# DIDV_-_Expansao_10.net
KiCad netlist of a schematic drawn in EAGLE
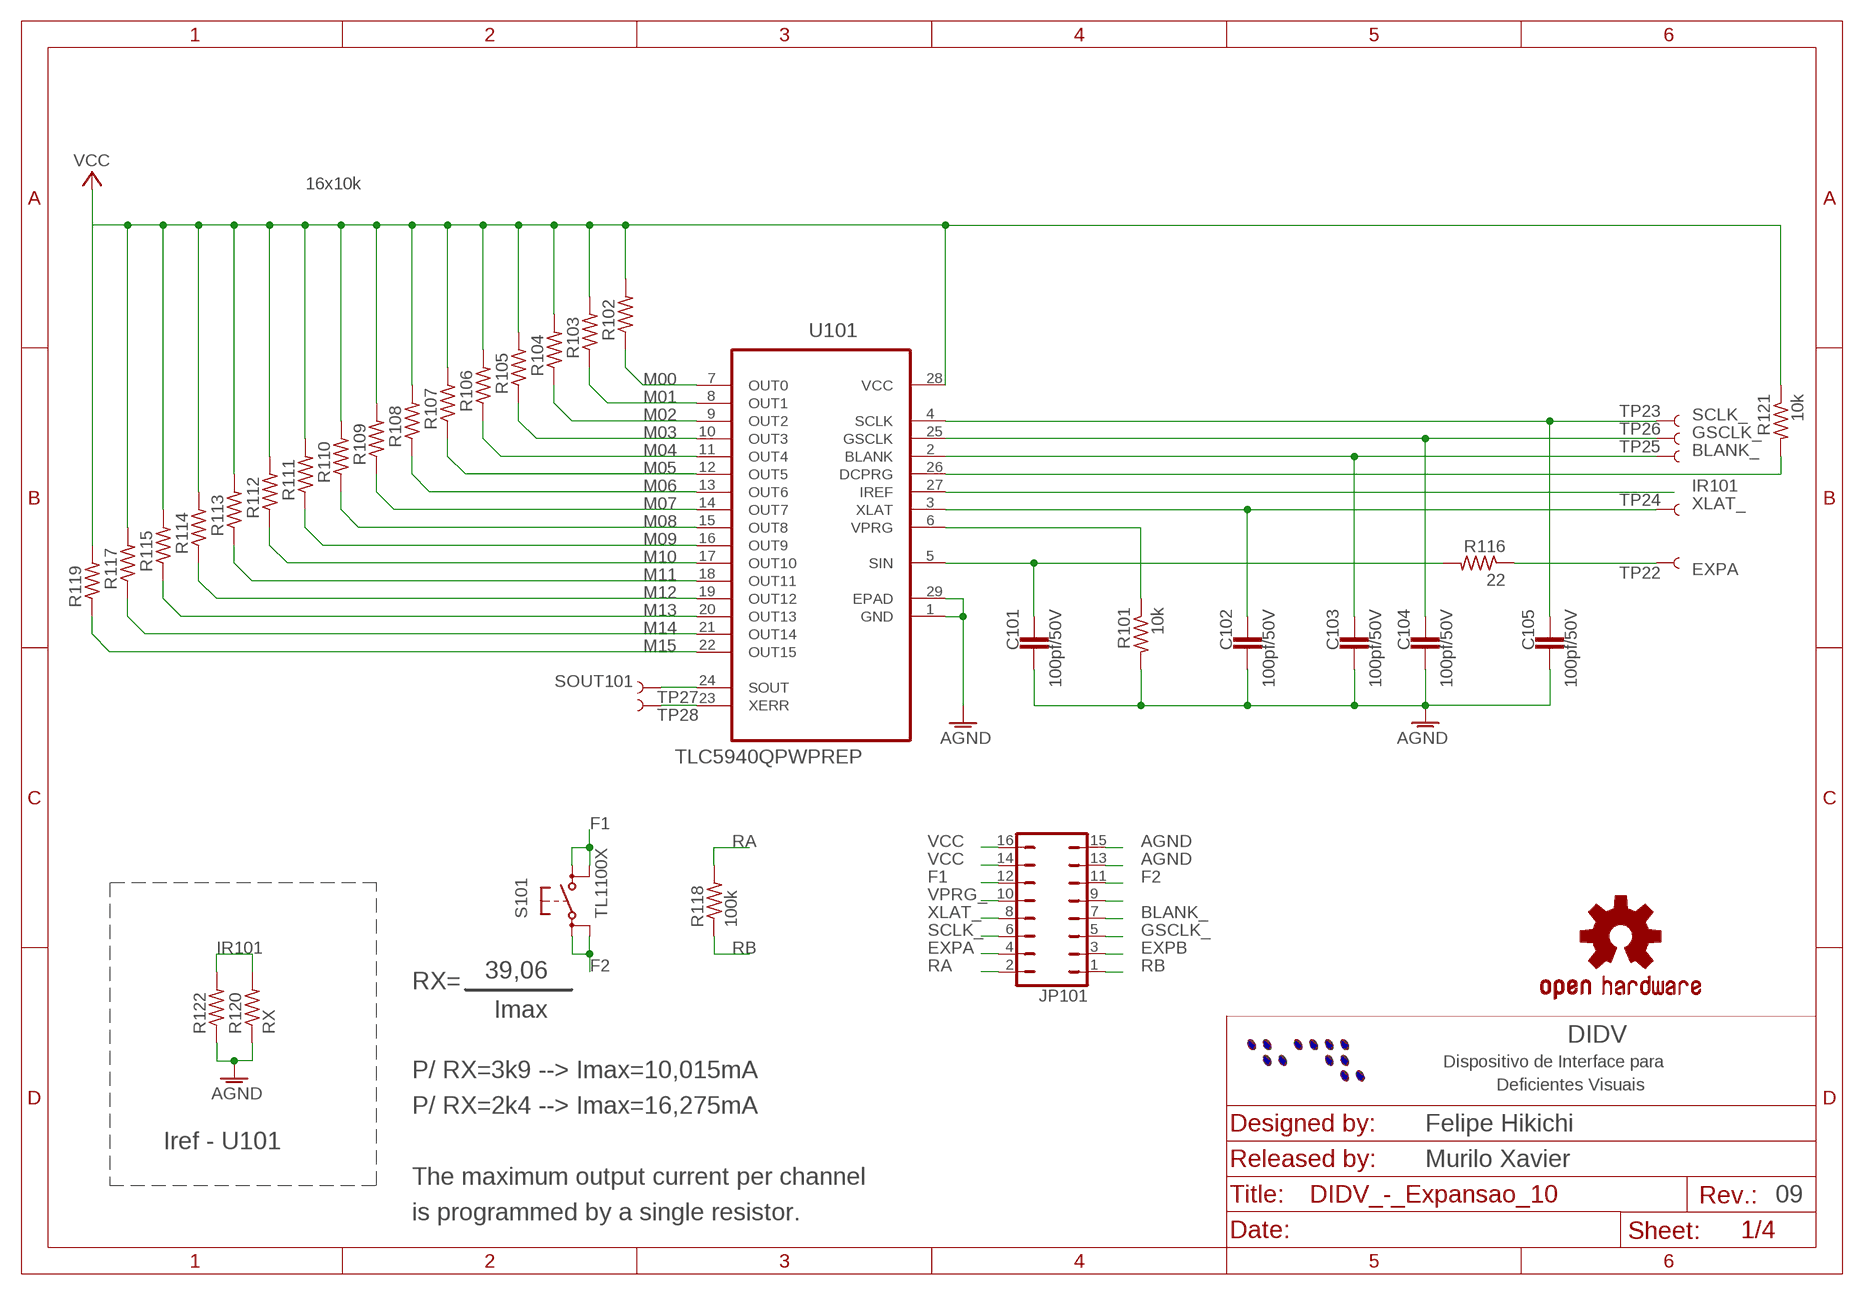
[diagram p0: schematic, sheet 1]
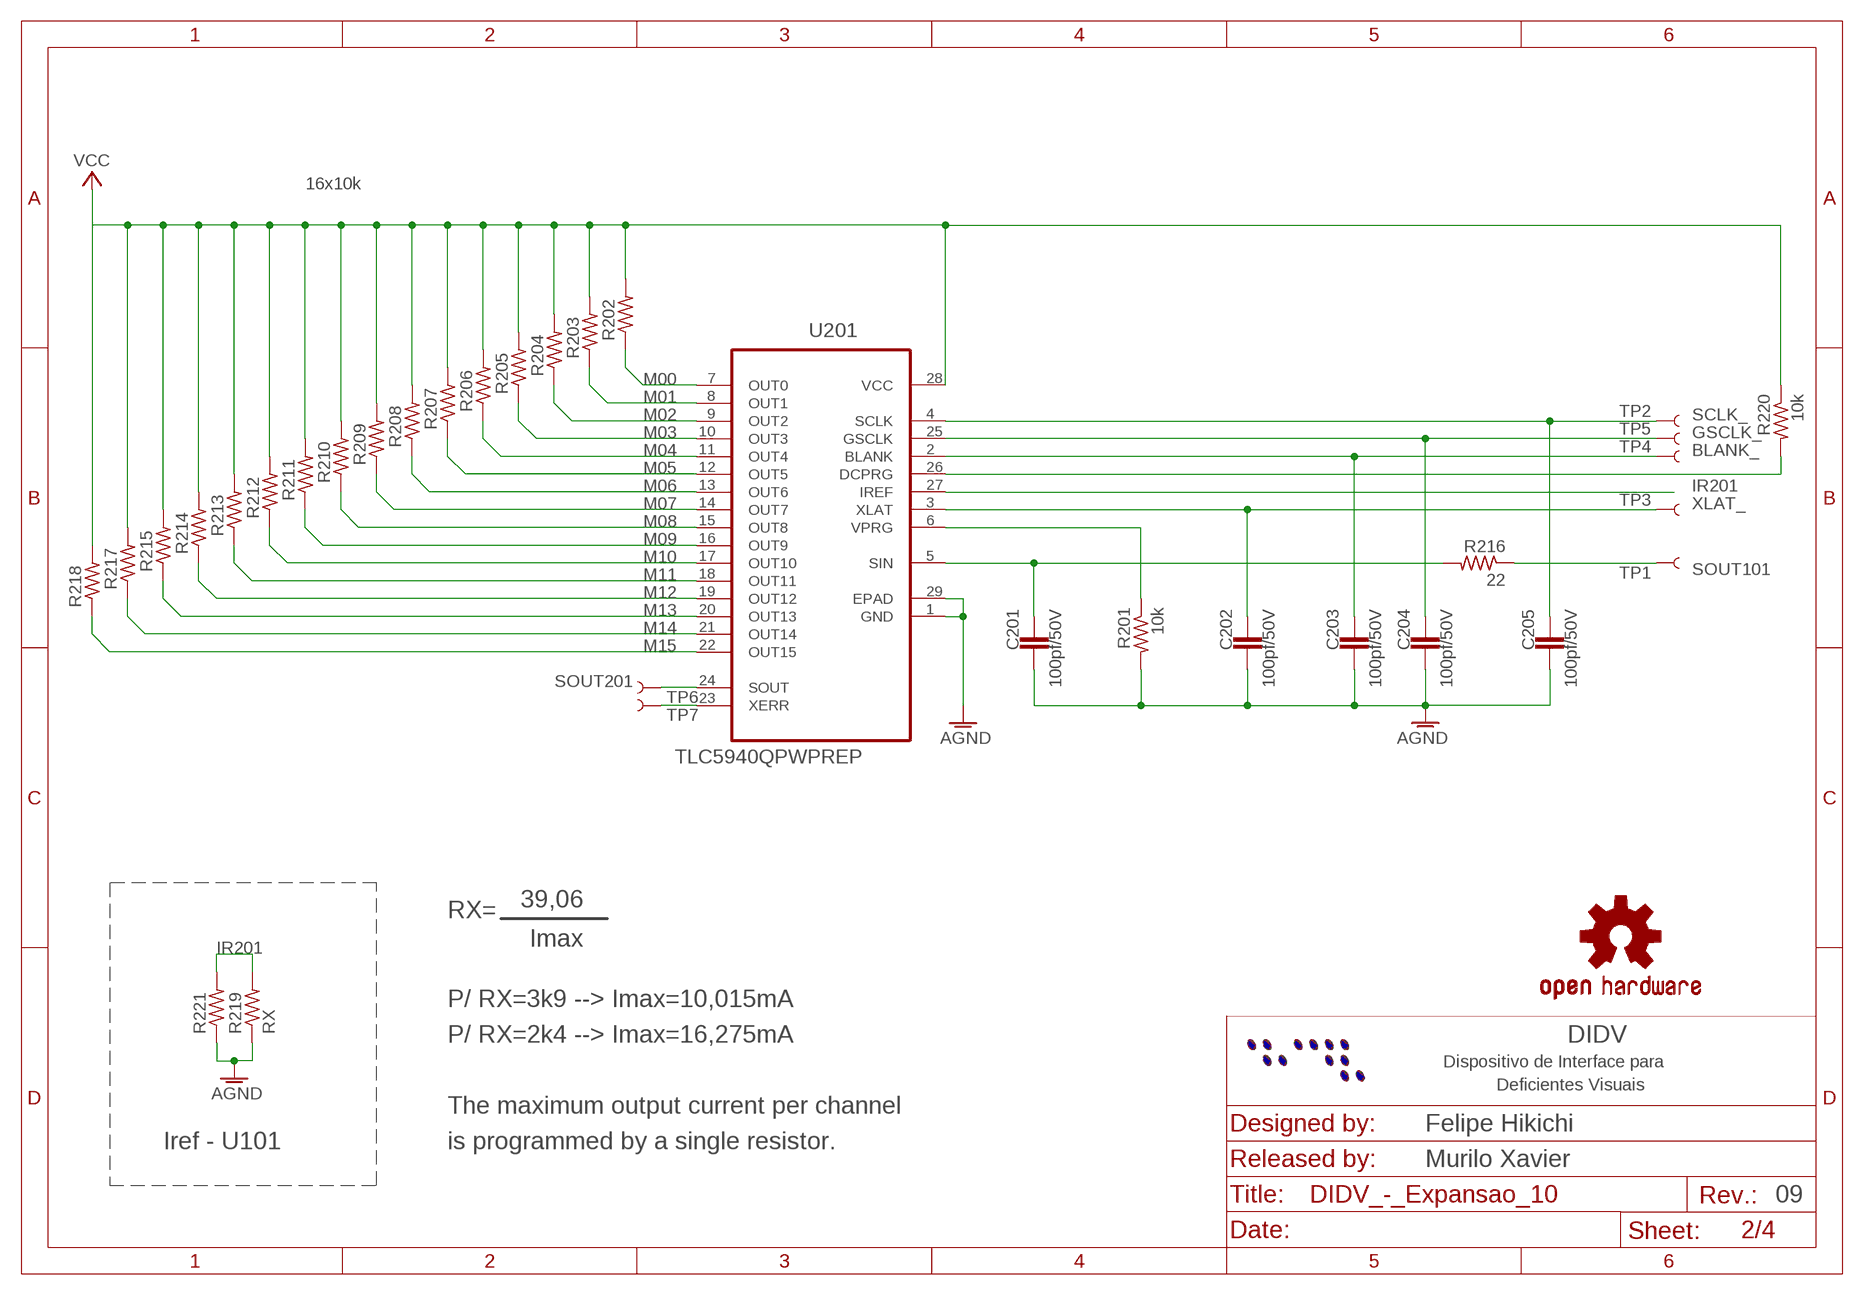
[diagram p1: schematic, sheet 2]
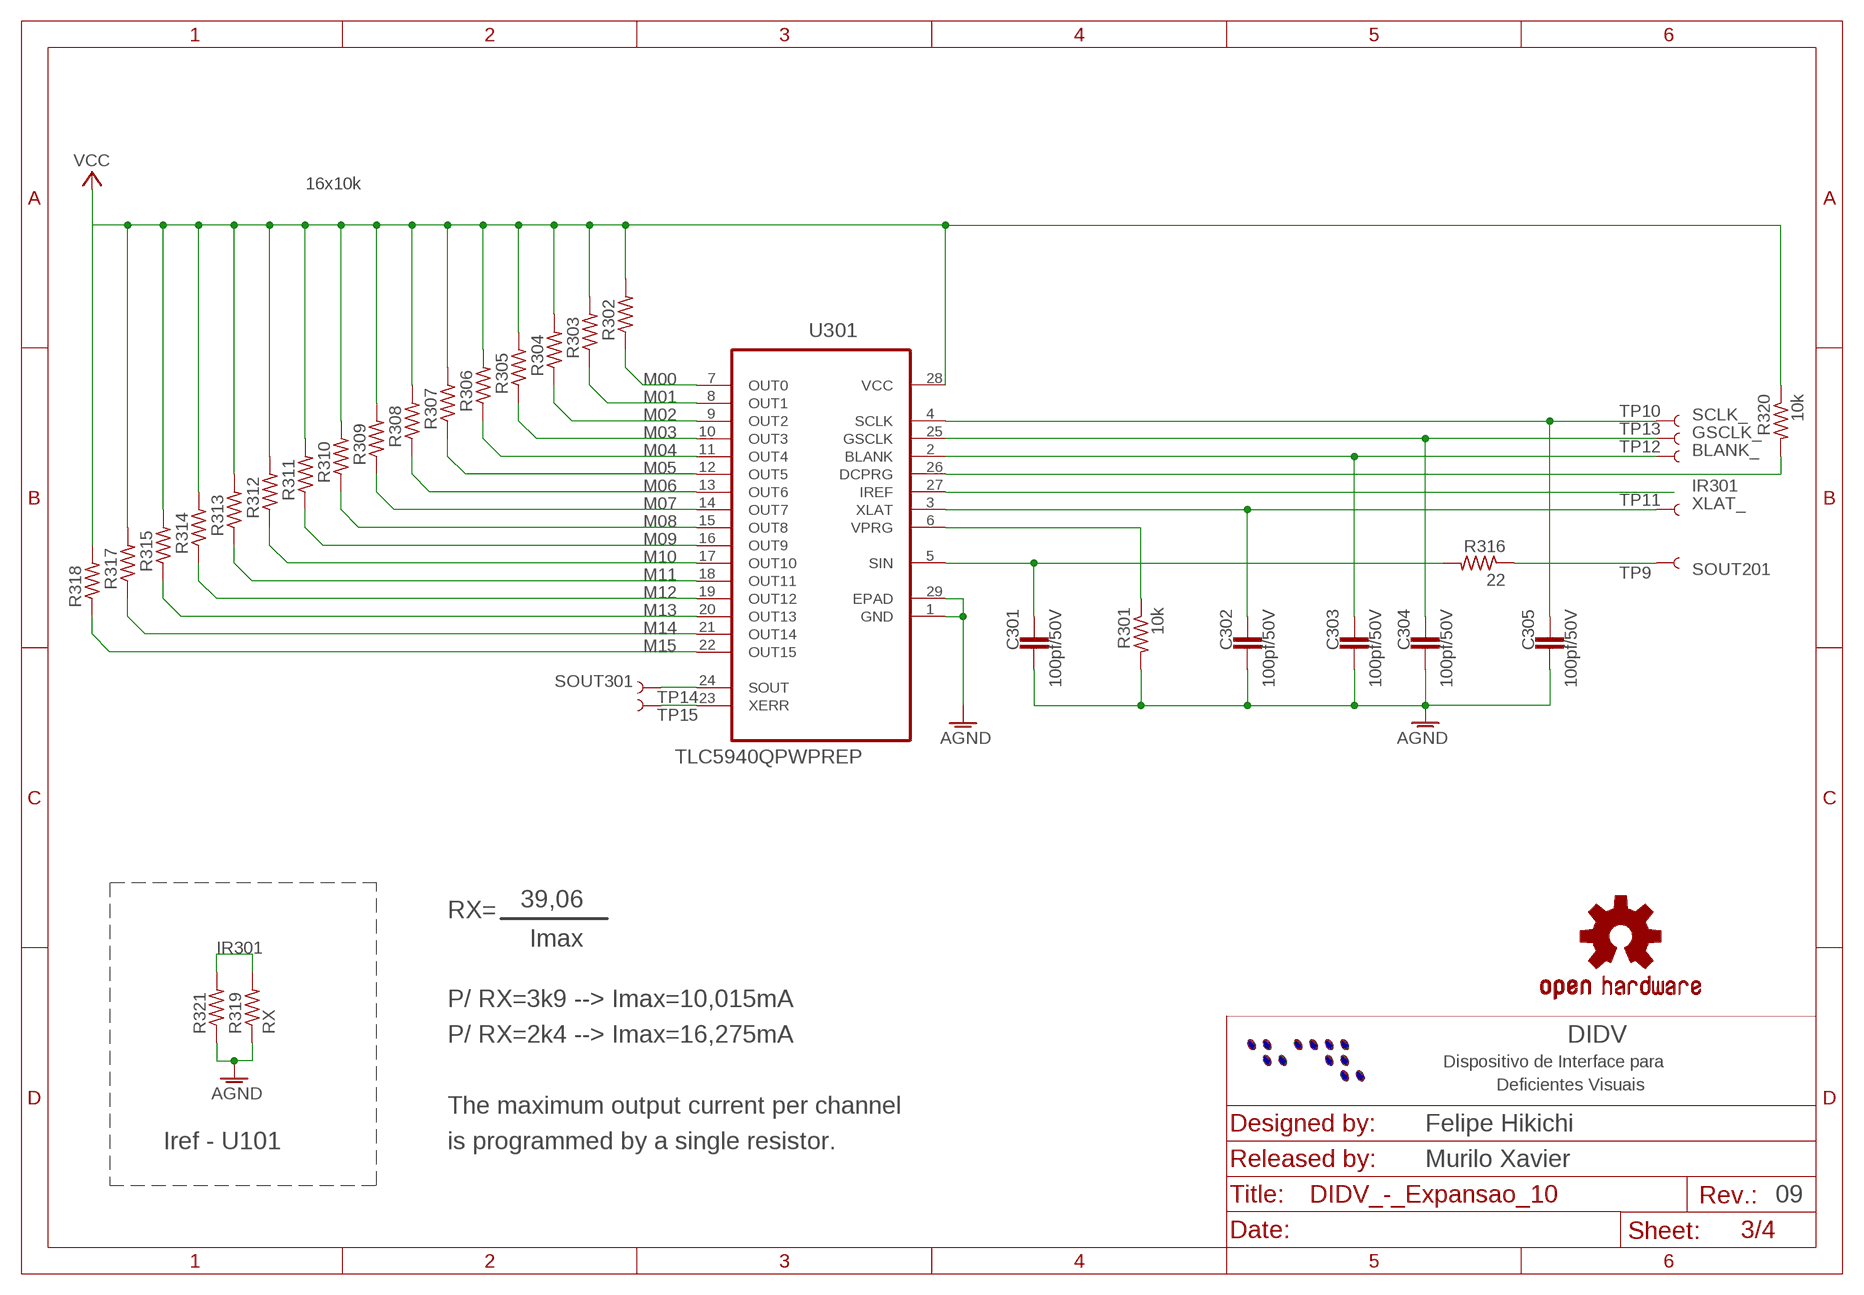
[diagram p2: schematic, sheet 3]
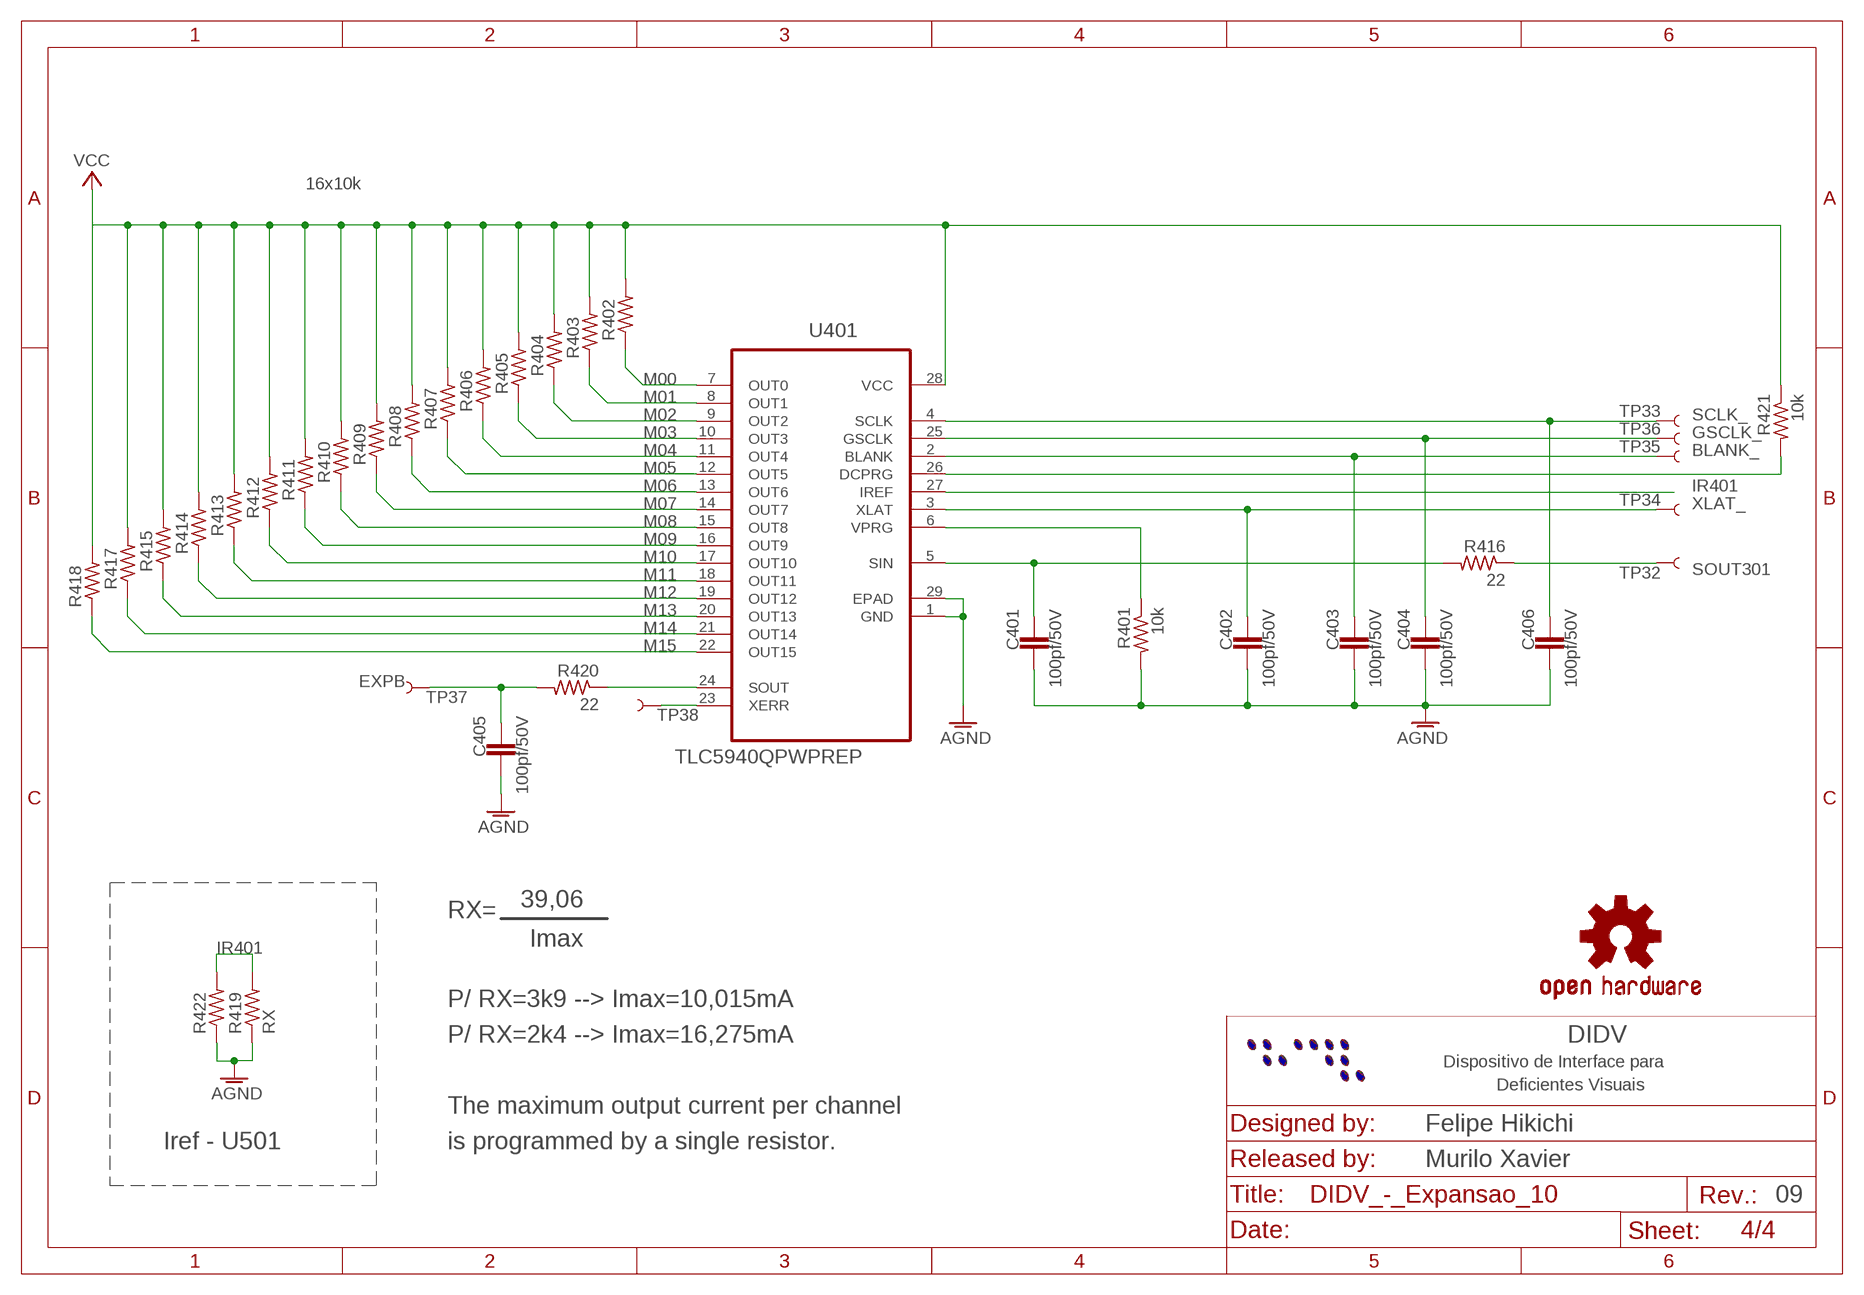
[diagram p3: schematic, sheet 4]

(export (version "E")
  (design (tool "Eeschema 10.0.6"))
  (components
    (comp (ref "C201")
      (value "100pf/50V")
      (footprint "eagle-import:C0603K")
      (libsource (lib "eagle-import") (part "C-EUC0603K"))
    )
    (comp (ref "C202")
      (value "100pf/50V")
      (footprint "eagle-import:C0603K")
      (libsource (lib "eagle-import") (part "C-EUC0603K"))
    )
    (comp (ref "C203")
      (value "100pf/50V")
      (footprint "eagle-import:C0603K")
      (libsource (lib "eagle-import") (part "C-EUC0603K"))
    )
    (comp (ref "C204")
      (value "100pf/50V")
      (footprint "eagle-import:C0603K")
      (libsource (lib "eagle-import") (part "C-EUC0603K"))
    )
    (comp (ref "C205")
      (value "100pf/50V")
      (footprint "eagle-import:C0603K")
      (libsource (lib "eagle-import") (part "C-EUC0603K"))
    )
    (comp (ref "LOGO201")
      (value "OSHW-LOGOM")
      (footprint "eagle-import:OSHW-LOGO-M")
      (libsource (lib "eagle-import") (part "OSHW-LOGOM"))
    )
    (comp (ref "R201")
      (value "10k")
      (footprint "eagle-import:R0603")
      (libsource (lib "eagle-import") (part "R-US_R0603"))
    )
    (comp (ref "R202")
      (value "R-US_R0805")
      (footprint "eagle-import:R0805")
      (libsource (lib "eagle-import") (part "R-US_R0805"))
    )
    (comp (ref "R203")
      (value "R-US_R0805")
      (footprint "eagle-import:R0805")
      (libsource (lib "eagle-import") (part "R-US_R0805"))
    )
    (comp (ref "R204")
      (value "R-US_R0805")
      (footprint "eagle-import:R0805")
      (libsource (lib "eagle-import") (part "R-US_R0805"))
    )
    (comp (ref "R205")
      (value "R-US_R0805")
      (footprint "eagle-import:R0805")
      (libsource (lib "eagle-import") (part "R-US_R0805"))
    )
    (comp (ref "R206")
      (value "R-US_R0805")
      (footprint "eagle-import:R0805")
      (libsource (lib "eagle-import") (part "R-US_R0805"))
    )
    (comp (ref "R207")
      (value "R-US_R0805")
      (footprint "eagle-import:R0805")
      (libsource (lib "eagle-import") (part "R-US_R0805"))
    )
    (comp (ref "R208")
      (value "R-US_R0805")
      (footprint "eagle-import:R0805")
      (libsource (lib "eagle-import") (part "R-US_R0805"))
    )
    (comp (ref "R209")
      (value "R-US_R0805")
      (footprint "eagle-import:R0805")
      (libsource (lib "eagle-import") (part "R-US_R0805"))
    )
    (comp (ref "R210")
      (value "R-US_R0805")
      (footprint "eagle-import:R0805")
      (libsource (lib "eagle-import") (part "R-US_R0805"))
    )
    (comp (ref "R211")
      (value "R-US_R0805")
      (footprint "eagle-import:R0805")
      (libsource (lib "eagle-import") (part "R-US_R0805"))
    )
    (comp (ref "R212")
      (value "R-US_R0805")
      (footprint "eagle-import:R0805")
      (libsource (lib "eagle-import") (part "R-US_R0805"))
    )
    (comp (ref "R213")
      (value "R-US_R0805")
      (footprint "eagle-import:R0805")
      (libsource (lib "eagle-import") (part "R-US_R0805"))
    )
    (comp (ref "R214")
      (value "R-US_R0805")
      (footprint "eagle-import:R0805")
      (libsource (lib "eagle-import") (part "R-US_R0805"))
    )
    (comp (ref "R215")
      (value "R-US_R0805")
      (footprint "eagle-import:R0805")
      (libsource (lib "eagle-import") (part "R-US_R0805"))
    )
    (comp (ref "R216")
      (value "22")
      (footprint "eagle-import:R0603")
      (libsource (lib "eagle-import") (part "R-US_R0603"))
    )
    (comp (ref "R217")
      (value "R-US_R0805")
      (footprint "eagle-import:R0805")
      (libsource (lib "eagle-import") (part "R-US_R0805"))
    )
    (comp (ref "R218")
      (value "R-US_R0805")
      (footprint "eagle-import:R0805")
      (libsource (lib "eagle-import") (part "R-US_R0805"))
    )
    (comp (ref "R219")
      (value "RX")
      (footprint "eagle-import:R0805")
      (libsource (lib "eagle-import") (part "R-US_R0805"))
    )
    (comp (ref "R220")
      (value "10k")
      (footprint "eagle-import:R0603")
      (libsource (lib "eagle-import") (part "R-US_R0603"))
    )
    (comp (ref "R221")
      (value "R-US_R0805")
      (footprint "eagle-import:R0805")
      (libsource (lib "eagle-import") (part "R-US_R0805"))
    )
    (comp (ref "TP1")
      (value "TEST-POINT3X4")
      (footprint "eagle-import:PAD.03X.04")
      (libsource (lib "eagle-import") (part "TEST-POINT3X4"))
    )
    (comp (ref "TP2")
      (value "TEST-POINT3X4")
      (footprint "eagle-import:PAD.03X.04")
      (libsource (lib "eagle-import") (part "TEST-POINT3X4"))
    )
    (comp (ref "TP3")
      (value "TEST-POINT3X4")
      (footprint "eagle-import:PAD.03X.04")
      (libsource (lib "eagle-import") (part "TEST-POINT3X4"))
    )
    (comp (ref "TP4")
      (value "TEST-POINT3X4")
      (footprint "eagle-import:PAD.03X.04")
      (libsource (lib "eagle-import") (part "TEST-POINT3X4"))
    )
    (comp (ref "TP5")
      (value "TEST-POINT3X4")
      (footprint "eagle-import:PAD.03X.04")
      (libsource (lib "eagle-import") (part "TEST-POINT3X4"))
    )
    (comp (ref "TP6")
      (value "TEST-POINT3X4")
      (footprint "eagle-import:PAD.03X.04")
      (libsource (lib "eagle-import") (part "TEST-POINT3X4"))
    )
    (comp (ref "TP7")
      (value "TEST-POINT3X4")
      (footprint "eagle-import:PAD.03X.04")
      (libsource (lib "eagle-import") (part "TEST-POINT3X4"))
    )
    (comp (ref "U201")
      (value "TLC5940QPWPREP")
      (footprint "eagle-import:SOP65P640X120-29N")
      (libsource (lib "eagle-import") (part "TLC5940QPWPREP"))
    )
    (comp (ref "C301")
      (value "100pf/50V")
      (footprint "eagle-import:C0603K")
      (libsource (lib "eagle-import") (part "C-EUC0603K"))
    )
    (comp (ref "C302")
      (value "100pf/50V")
      (footprint "eagle-import:C0603K")
      (libsource (lib "eagle-import") (part "C-EUC0603K"))
    )
    (comp (ref "C303")
      (value "100pf/50V")
      (footprint "eagle-import:C0603K")
      (libsource (lib "eagle-import") (part "C-EUC0603K"))
    )
    (comp (ref "C304")
      (value "100pf/50V")
      (footprint "eagle-import:C0603K")
      (libsource (lib "eagle-import") (part "C-EUC0603K"))
    )
    (comp (ref "C305")
      (value "100pf/50V")
      (footprint "eagle-import:C0603K")
      (libsource (lib "eagle-import") (part "C-EUC0603K"))
    )
    (comp (ref "LOGO301")
      (value "OSHW-LOGOM")
      (footprint "eagle-import:OSHW-LOGO-M")
      (libsource (lib "eagle-import") (part "OSHW-LOGOM"))
    )
    (comp (ref "R301")
      (value "10k")
      (footprint "eagle-import:R0603")
      (libsource (lib "eagle-import") (part "R-US_R0603"))
    )
    (comp (ref "R302")
      (value "R-US_R0805")
      (footprint "eagle-import:R0805")
      (libsource (lib "eagle-import") (part "R-US_R0805"))
    )
    (comp (ref "R303")
      (value "R-US_R0805")
      (footprint "eagle-import:R0805")
      (libsource (lib "eagle-import") (part "R-US_R0805"))
    )
    (comp (ref "R304")
      (value "R-US_R0805")
      (footprint "eagle-import:R0805")
      (libsource (lib "eagle-import") (part "R-US_R0805"))
    )
    (comp (ref "R305")
      (value "R-US_R0805")
      (footprint "eagle-import:R0805")
      (libsource (lib "eagle-import") (part "R-US_R0805"))
    )
    (comp (ref "R306")
      (value "R-US_R0805")
      (footprint "eagle-import:R0805")
      (libsource (lib "eagle-import") (part "R-US_R0805"))
    )
    (comp (ref "R307")
      (value "R-US_R0805")
      (footprint "eagle-import:R0805")
      (libsource (lib "eagle-import") (part "R-US_R0805"))
    )
    (comp (ref "R308")
      (value "R-US_R0805")
      (footprint "eagle-import:R0805")
      (libsource (lib "eagle-import") (part "R-US_R0805"))
    )
    (comp (ref "R309")
      (value "R-US_R0805")
      (footprint "eagle-import:R0805")
      (libsource (lib "eagle-import") (part "R-US_R0805"))
    )
    (comp (ref "R310")
      (value "R-US_R0805")
      (footprint "eagle-import:R0805")
      (libsource (lib "eagle-import") (part "R-US_R0805"))
    )
    (comp (ref "R311")
      (value "R-US_R0805")
      (footprint "eagle-import:R0805")
      (libsource (lib "eagle-import") (part "R-US_R0805"))
    )
    (comp (ref "R312")
      (value "R-US_R0805")
      (footprint "eagle-import:R0805")
      (libsource (lib "eagle-import") (part "R-US_R0805"))
    )
    (comp (ref "R313")
      (value "R-US_R0805")
      (footprint "eagle-import:R0805")
      (libsource (lib "eagle-import") (part "R-US_R0805"))
    )
    (comp (ref "R314")
      (value "R-US_R0805")
      (footprint "eagle-import:R0805")
      (libsource (lib "eagle-import") (part "R-US_R0805"))
    )
    (comp (ref "R315")
      (value "R-US_R0805")
      (footprint "eagle-import:R0805")
      (libsource (lib "eagle-import") (part "R-US_R0805"))
    )
    (comp (ref "R316")
      (value "22")
      (footprint "eagle-import:R0603")
      (libsource (lib "eagle-import") (part "R-US_R0603"))
    )
    (comp (ref "R317")
      (value "R-US_R0805")
      (footprint "eagle-import:R0805")
      (libsource (lib "eagle-import") (part "R-US_R0805"))
    )
    (comp (ref "R318")
      (value "R-US_R0805")
      (footprint "eagle-import:R0805")
      (libsource (lib "eagle-import") (part "R-US_R0805"))
    )
    (comp (ref "R319")
      (value "RX")
      (footprint "eagle-import:R0805")
      (libsource (lib "eagle-import") (part "R-US_R0805"))
    )
    (comp (ref "R320")
      (value "10k")
      (footprint "eagle-import:R0603")
      (libsource (lib "eagle-import") (part "R-US_R0603"))
    )
    (comp (ref "R321")
      (value "R-US_R0805")
      (footprint "eagle-import:R0805")
      (libsource (lib "eagle-import") (part "R-US_R0805"))
    )
    (comp (ref "TP9")
      (value "TEST-POINT3X4")
      (footprint "eagle-import:PAD.03X.04")
      (libsource (lib "eagle-import") (part "TEST-POINT3X4"))
    )
    (comp (ref "TP10")
      (value "TEST-POINT3X4")
      (footprint "eagle-import:PAD.03X.04")
      (libsource (lib "eagle-import") (part "TEST-POINT3X4"))
    )
    (comp (ref "TP11")
      (value "TEST-POINT3X4")
      (footprint "eagle-import:PAD.03X.04")
      (libsource (lib "eagle-import") (part "TEST-POINT3X4"))
    )
    (comp (ref "TP12")
      (value "TEST-POINT3X4")
      (footprint "eagle-import:PAD.03X.04")
      (libsource (lib "eagle-import") (part "TEST-POINT3X4"))
    )
    (comp (ref "TP13")
      (value "TEST-POINT3X4")
      (footprint "eagle-import:PAD.03X.04")
      (libsource (lib "eagle-import") (part "TEST-POINT3X4"))
    )
    (comp (ref "TP14")
      (value "TEST-POINT3X4")
      (footprint "eagle-import:PAD.03X.04")
      (libsource (lib "eagle-import") (part "TEST-POINT3X4"))
    )
    (comp (ref "TP15")
      (value "TEST-POINT3X4")
      (footprint "eagle-import:PAD.03X.04")
      (libsource (lib "eagle-import") (part "TEST-POINT3X4"))
    )
    (comp (ref "U301")
      (value "TLC5940QPWPREP")
      (footprint "eagle-import:SOP65P640X120-29N")
      (libsource (lib "eagle-import") (part "TLC5940QPWPREP"))
    )
    (comp (ref "C101")
      (value "100pf/50V")
      (footprint "eagle-import:C0603K")
      (libsource (lib "eagle-import") (part "C-EUC0603K"))
    )
    (comp (ref "C102")
      (value "100pf/50V")
      (footprint "eagle-import:C0603K")
      (libsource (lib "eagle-import") (part "C-EUC0603K"))
    )
    (comp (ref "C103")
      (value "100pf/50V")
      (footprint "eagle-import:C0603K")
      (libsource (lib "eagle-import") (part "C-EUC0603K"))
    )
    (comp (ref "C104")
      (value "100pf/50V")
      (footprint "eagle-import:C0603K")
      (libsource (lib "eagle-import") (part "C-EUC0603K"))
    )
    (comp (ref "C105")
      (value "100pf/50V")
      (footprint "eagle-import:C0603K")
      (libsource (lib "eagle-import") (part "C-EUC0603K"))
    )
    (comp (ref "JP101")
      (value "JP8Q")
      (footprint "eagle-import:JP8Q")
      (libsource (lib "eagle-import") (part "JP8Q"))
    )
    (comp (ref "LOGO101")
      (value "OSHW-LOGOM")
      (footprint "eagle-import:OSHW-LOGO-M")
      (libsource (lib "eagle-import") (part "OSHW-LOGOM"))
    )
    (comp (ref "R101")
      (value "10k")
      (footprint "eagle-import:R0603")
      (libsource (lib "eagle-import") (part "R-US_R0603"))
    )
    (comp (ref "R102")
      (value "R-US_R0805")
      (footprint "eagle-import:R0805")
      (libsource (lib "eagle-import") (part "R-US_R0805"))
    )
    (comp (ref "R103")
      (value "R-US_R0805")
      (footprint "eagle-import:R0805")
      (libsource (lib "eagle-import") (part "R-US_R0805"))
    )
    (comp (ref "R104")
      (value "R-US_R0805")
      (footprint "eagle-import:R0805")
      (libsource (lib "eagle-import") (part "R-US_R0805"))
    )
    (comp (ref "R105")
      (value "R-US_R0805")
      (footprint "eagle-import:R0805")
      (libsource (lib "eagle-import") (part "R-US_R0805"))
    )
    (comp (ref "R106")
      (value "R-US_R0805")
      (footprint "eagle-import:R0805")
      (libsource (lib "eagle-import") (part "R-US_R0805"))
    )
    (comp (ref "R107")
      (value "R-US_R0805")
      (footprint "eagle-import:R0805")
      (libsource (lib "eagle-import") (part "R-US_R0805"))
    )
    (comp (ref "R108")
      (value "R-US_R0805")
      (footprint "eagle-import:R0805")
      (libsource (lib "eagle-import") (part "R-US_R0805"))
    )
    (comp (ref "R109")
      (value "R-US_R0805")
      (footprint "eagle-import:R0805")
      (libsource (lib "eagle-import") (part "R-US_R0805"))
    )
    (comp (ref "R110")
      (value "R-US_R0805")
      (footprint "eagle-import:R0805")
      (libsource (lib "eagle-import") (part "R-US_R0805"))
    )
    (comp (ref "R111")
      (value "R-US_R0805")
      (footprint "eagle-import:R0805")
      (libsource (lib "eagle-import") (part "R-US_R0805"))
    )
    (comp (ref "R112")
      (value "R-US_R0805")
      (footprint "eagle-import:R0805")
      (libsource (lib "eagle-import") (part "R-US_R0805"))
    )
    (comp (ref "R113")
      (value "R-US_R0805")
      (footprint "eagle-import:R0805")
      (libsource (lib "eagle-import") (part "R-US_R0805"))
    )
    (comp (ref "R114")
      (value "R-US_R0805")
      (footprint "eagle-import:R0805")
      (libsource (lib "eagle-import") (part "R-US_R0805"))
    )
    (comp (ref "R115")
      (value "R-US_R0805")
      (footprint "eagle-import:R0805")
      (libsource (lib "eagle-import") (part "R-US_R0805"))
    )
    (comp (ref "R116")
      (value "22")
      (footprint "eagle-import:R0603")
      (libsource (lib "eagle-import") (part "R-US_R0603"))
    )
    (comp (ref "R117")
      (value "R-US_R0805")
      (footprint "eagle-import:R0805")
      (libsource (lib "eagle-import") (part "R-US_R0805"))
    )
    (comp (ref "R118")
      (value "100k")
      (footprint "eagle-import:R0805")
      (libsource (lib "eagle-import") (part "R-US_R0805"))
    )
    (comp (ref "R119")
      (value "R-US_R0805")
      (footprint "eagle-import:R0805")
      (libsource (lib "eagle-import") (part "R-US_R0805"))
    )
    (comp (ref "R120")
      (value "RX")
      (footprint "eagle-import:R0805")
      (libsource (lib "eagle-import") (part "R-US_R0805"))
    )
    (comp (ref "R121")
      (value "10k")
      (footprint "eagle-import:R0603")
      (libsource (lib "eagle-import") (part "R-US_R0603"))
    )
    (comp (ref "R122")
      (value "R-US_R0805")
      (footprint "eagle-import:R0805")
      (libsource (lib "eagle-import") (part "R-US_R0805"))
    )
    (comp (ref "S101")
      (value "TL1100X")
      (footprint "eagle-import:TL1100X")
      (libsource (lib "eagle-import") (part "TL1100X"))
    )
    (comp (ref "TP22")
      (value "TEST-POINT3X4")
      (footprint "eagle-import:PAD.03X.04")
      (libsource (lib "eagle-import") (part "TEST-POINT3X4"))
    )
    (comp (ref "TP23")
      (value "TEST-POINT3X4")
      (footprint "eagle-import:PAD.03X.04")
      (libsource (lib "eagle-import") (part "TEST-POINT3X4"))
    )
    (comp (ref "TP24")
      (value "TEST-POINT3X4")
      (footprint "eagle-import:PAD.03X.04")
      (libsource (lib "eagle-import") (part "TEST-POINT3X4"))
    )
    (comp (ref "TP25")
      (value "TEST-POINT3X4")
      (footprint "eagle-import:PAD.03X.04")
      (libsource (lib "eagle-import") (part "TEST-POINT3X4"))
    )
    (comp (ref "TP26")
      (value "TEST-POINT3X4")
      (footprint "eagle-import:PAD.03X.04")
      (libsource (lib "eagle-import") (part "TEST-POINT3X4"))
    )
    (comp (ref "TP27")
      (value "TEST-POINT3X4")
      (footprint "eagle-import:PAD.03X.04")
      (libsource (lib "eagle-import") (part "TEST-POINT3X4"))
    )
    (comp (ref "TP28")
      (value "TEST-POINT3X4")
      (footprint "eagle-import:PAD.03X.04")
      (libsource (lib "eagle-import") (part "TEST-POINT3X4"))
    )
    (comp (ref "U101")
      (value "TLC5940QPWPREP")
      (footprint "eagle-import:SOP65P640X120-29N")
      (libsource (lib "eagle-import") (part "TLC5940QPWPREP"))
    )
    (comp (ref "C401")
      (value "100pf/50V")
      (footprint "eagle-import:C0603K")
      (libsource (lib "eagle-import") (part "C-EUC0603K"))
    )
    (comp (ref "C402")
      (value "100pf/50V")
      (footprint "eagle-import:C0603K")
      (libsource (lib "eagle-import") (part "C-EUC0603K"))
    )
    (comp (ref "C403")
      (value "100pf/50V")
      (footprint "eagle-import:C0603K")
      (libsource (lib "eagle-import") (part "C-EUC0603K"))
    )
    (comp (ref "C404")
      (value "100pf/50V")
      (footprint "eagle-import:C0603K")
      (libsource (lib "eagle-import") (part "C-EUC0603K"))
    )
    (comp (ref "C405")
      (value "100pf/50V")
      (footprint "eagle-import:C0603K")
      (libsource (lib "eagle-import") (part "C-EUC0603K"))
    )
    (comp (ref "C406")
      (value "100pf/50V")
      (footprint "eagle-import:C0603K")
      (libsource (lib "eagle-import") (part "C-EUC0603K"))
    )
    (comp (ref "LOGO401")
      (value "OSHW-LOGOM")
      (footprint "eagle-import:OSHW-LOGO-M")
      (libsource (lib "eagle-import") (part "OSHW-LOGOM"))
    )
    (comp (ref "R401")
      (value "10k")
      (footprint "eagle-import:R0603")
      (libsource (lib "eagle-import") (part "R-US_R0603"))
    )
    (comp (ref "R402")
      (value "R-US_R0805")
      (footprint "eagle-import:R0805")
      (libsource (lib "eagle-import") (part "R-US_R0805"))
    )
    (comp (ref "R403")
      (value "R-US_R0805")
      (footprint "eagle-import:R0805")
      (libsource (lib "eagle-import") (part "R-US_R0805"))
    )
    (comp (ref "R404")
      (value "R-US_R0805")
      (footprint "eagle-import:R0805")
      (libsource (lib "eagle-import") (part "R-US_R0805"))
    )
    (comp (ref "R405")
      (value "R-US_R0805")
      (footprint "eagle-import:R0805")
      (libsource (lib "eagle-import") (part "R-US_R0805"))
    )
    (comp (ref "R406")
      (value "R-US_R0805")
      (footprint "eagle-import:R0805")
      (libsource (lib "eagle-import") (part "R-US_R0805"))
    )
    (comp (ref "R407")
      (value "R-US_R0805")
      (footprint "eagle-import:R0805")
      (libsource (lib "eagle-import") (part "R-US_R0805"))
    )
    (comp (ref "R408")
      (value "R-US_R0805")
      (footprint "eagle-import:R0805")
      (libsource (lib "eagle-import") (part "R-US_R0805"))
    )
    (comp (ref "R409")
      (value "R-US_R0805")
      (footprint "eagle-import:R0805")
      (libsource (lib "eagle-import") (part "R-US_R0805"))
    )
    (comp (ref "R410")
      (value "R-US_R0805")
      (footprint "eagle-import:R0805")
      (libsource (lib "eagle-import") (part "R-US_R0805"))
    )
    (comp (ref "R411")
      (value "R-US_R0805")
      (footprint "eagle-import:R0805")
      (libsource (lib "eagle-import") (part "R-US_R0805"))
    )
    (comp (ref "R412")
      (value "R-US_R0805")
      (footprint "eagle-import:R0805")
      (libsource (lib "eagle-import") (part "R-US_R0805"))
    )
    (comp (ref "R413")
      (value "R-US_R0805")
      (footprint "eagle-import:R0805")
      (libsource (lib "eagle-import") (part "R-US_R0805"))
    )
    (comp (ref "R414")
      (value "R-US_R0805")
      (footprint "eagle-import:R0805")
      (libsource (lib "eagle-import") (part "R-US_R0805"))
    )
    (comp (ref "R415")
      (value "R-US_R0805")
      (footprint "eagle-import:R0805")
      (libsource (lib "eagle-import") (part "R-US_R0805"))
    )
    (comp (ref "R416")
      (value "22")
      (footprint "eagle-import:R0603")
      (libsource (lib "eagle-import") (part "R-US_R0603"))
    )
    (comp (ref "R417")
      (value "R-US_R0805")
      (footprint "eagle-import:R0805")
      (libsource (lib "eagle-import") (part "R-US_R0805"))
    )
    (comp (ref "R418")
      (value "R-US_R0805")
      (footprint "eagle-import:R0805")
      (libsource (lib "eagle-import") (part "R-US_R0805"))
    )
    (comp (ref "R419")
      (value "RX")
      (footprint "eagle-import:R0805")
      (libsource (lib "eagle-import") (part "R-US_R0805"))
    )
    (comp (ref "R420")
      (value "22")
      (footprint "eagle-import:R0603")
      (libsource (lib "eagle-import") (part "R-US_R0603"))
    )
    (comp (ref "R421")
      (value "10k")
      (footprint "eagle-import:R0603")
      (libsource (lib "eagle-import") (part "R-US_R0603"))
    )
    (comp (ref "R422")
      (value "R-US_R0805")
      (footprint "eagle-import:R0805")
      (libsource (lib "eagle-import") (part "R-US_R0805"))
    )
    (comp (ref "TP32")
      (value "TEST-POINT3X4")
      (footprint "eagle-import:PAD.03X.04")
      (libsource (lib "eagle-import") (part "TEST-POINT3X4"))
    )
    (comp (ref "TP33")
      (value "TEST-POINT3X4")
      (footprint "eagle-import:PAD.03X.04")
      (libsource (lib "eagle-import") (part "TEST-POINT3X4"))
    )
    (comp (ref "TP34")
      (value "TEST-POINT3X4")
      (footprint "eagle-import:PAD.03X.04")
      (libsource (lib "eagle-import") (part "TEST-POINT3X4"))
    )
    (comp (ref "TP35")
      (value "TEST-POINT3X4")
      (footprint "eagle-import:PAD.03X.04")
      (libsource (lib "eagle-import") (part "TEST-POINT3X4"))
    )
    (comp (ref "TP36")
      (value "TEST-POINT3X4")
      (footprint "eagle-import:PAD.03X.04")
      (libsource (lib "eagle-import") (part "TEST-POINT3X4"))
    )
    (comp (ref "TP37")
      (value "TEST-POINT3X4")
      (footprint "eagle-import:PAD.03X.04")
      (libsource (lib "eagle-import") (part "TEST-POINT3X4"))
    )
    (comp (ref "TP38")
      (value "TEST-POINT3X4")
      (footprint "eagle-import:PAD.03X.04")
      (libsource (lib "eagle-import") (part "TEST-POINT3X4"))
    )
    (comp (ref "U401")
      (value "TLC5940QPWPREP")
      (footprint "eagle-import:SOP65P640X120-29N")
      (libsource (lib "eagle-import") (part "TLC5940QPWPREP"))
    )
  )
  (nets
    (net (code "1") (name "AGND") (class "Default")
      (node (ref "C101") (pin "1") (pinfunction "1_1") (pintype "passive"))
      (node (ref "C102") (pin "1") (pinfunction "1_1") (pintype "passive"))
      (node (ref "C103") (pin "1") (pinfunction "1_1") (pintype "passive"))
      (node (ref "C104") (pin "1") (pinfunction "1_1") (pintype "passive"))
      (node (ref "C105") (pin "1") (pinfunction "1_1") (pintype "passive"))
      (node (ref "C201") (pin "1") (pinfunction "1_1") (pintype "passive"))
      (node (ref "C202") (pin "1") (pinfunction "1_1") (pintype "passive"))
      (node (ref "C203") (pin "1") (pinfunction "1_1") (pintype "passive"))
      (node (ref "C204") (pin "1") (pinfunction "1_1") (pintype "passive"))
      (node (ref "C205") (pin "1") (pinfunction "1_1") (pintype "passive"))
      (node (ref "C301") (pin "1") (pinfunction "1_1") (pintype "passive"))
      (node (ref "C302") (pin "1") (pinfunction "1_1") (pintype "passive"))
      (node (ref "C303") (pin "1") (pinfunction "1_1") (pintype "passive"))
      (node (ref "C304") (pin "1") (pinfunction "1_1") (pintype "passive"))
      (node (ref "C305") (pin "1") (pinfunction "1_1") (pintype "passive"))
      (node (ref "C401") (pin "1") (pinfunction "1_1") (pintype "passive"))
      (node (ref "C402") (pin "1") (pinfunction "1_1") (pintype "passive"))
      (node (ref "C403") (pin "1") (pinfunction "1_1") (pintype "passive"))
      (node (ref "C404") (pin "1") (pinfunction "1_1") (pintype "passive"))
      (node (ref "C405") (pin "1") (pinfunction "1_1") (pintype "passive"))
      (node (ref "C406") (pin "1") (pinfunction "1_1") (pintype "passive"))
      (node (ref "JP101") (pin "13") (pinfunction "13_13") (pintype "passive"))
      (node (ref "JP101") (pin "15") (pinfunction "15_15") (pintype "passive"))
      (node (ref "R101") (pin "2") (pinfunction "2_2") (pintype "passive"))
      (node (ref "R120") (pin "1") (pinfunction "1_1") (pintype "passive"))
      (node (ref "R122") (pin "1") (pinfunction "1_1") (pintype "passive"))
      (node (ref "R201") (pin "2") (pinfunction "2_2") (pintype "passive"))
      (node (ref "R219") (pin "1") (pinfunction "1_1") (pintype "passive"))
      (node (ref "R221") (pin "1") (pinfunction "1_1") (pintype "passive"))
      (node (ref "R301") (pin "2") (pinfunction "2_2") (pintype "passive"))
      (node (ref "R319") (pin "1") (pinfunction "1_1") (pintype "passive"))
      (node (ref "R321") (pin "1") (pinfunction "1_1") (pintype "passive"))
      (node (ref "R401") (pin "2") (pinfunction "2_2") (pintype "passive"))
      (node (ref "R419") (pin "1") (pinfunction "1_1") (pintype "passive"))
      (node (ref "R422") (pin "1") (pinfunction "1_1") (pintype "passive"))
      (node (ref "U101") (pin "1") (pinfunction "GND_1") (pintype "passive"))
      (node (ref "U101") (pin "29") (pinfunction "EPAD_29") (pintype "passive"))
      (node (ref "U201") (pin "1") (pinfunction "GND_1") (pintype "passive"))
      (node (ref "U201") (pin "29") (pinfunction "EPAD_29") (pintype "passive"))
      (node (ref "U301") (pin "1") (pinfunction "GND_1") (pintype "passive"))
      (node (ref "U301") (pin "29") (pinfunction "EPAD_29") (pintype "passive"))
      (node (ref "U401") (pin "1") (pinfunction "GND_1") (pintype "passive"))
      (node (ref "U401") (pin "29") (pinfunction "EPAD_29") (pintype "passive"))
    )
    (net (code "2") (name "BLANK_") (class "Default")
      (node (ref "C103") (pin "2") (pinfunction "2_2") (pintype "passive"))
      (node (ref "C203") (pin "2") (pinfunction "2_2") (pintype "passive"))
      (node (ref "C303") (pin "2") (pinfunction "2_2") (pintype "passive"))
      (node (ref "C403") (pin "2") (pinfunction "2_2") (pintype "passive"))
      (node (ref "JP101") (pin "7") (pinfunction "7_7") (pintype "passive"))
      (node (ref "TP12") (pin "P$1") (pinfunction "1_P$1") (pintype "bidirectional"))
      (node (ref "TP25") (pin "P$1") (pinfunction "1_P$1") (pintype "bidirectional"))
      (node (ref "TP35") (pin "P$1") (pinfunction "1_P$1") (pintype "bidirectional"))
      (node (ref "TP4") (pin "P$1") (pinfunction "1_P$1") (pintype "bidirectional"))
      (node (ref "U101") (pin "2") (pinfunction "BLANK_2") (pintype "input"))
      (node (ref "U201") (pin "2") (pinfunction "BLANK_2") (pintype "input"))
      (node (ref "U301") (pin "2") (pinfunction "BLANK_2") (pintype "input"))
      (node (ref "U401") (pin "2") (pinfunction "BLANK_2") (pintype "input"))
    )
    (net (code "3") (name "EXPA") (class "Default")
      (node (ref "JP101") (pin "4") (pinfunction "4_4") (pintype "passive"))
      (node (ref "R116") (pin "1") (pinfunction "1_1") (pintype "passive"))
      (node (ref "TP22") (pin "P$1") (pinfunction "1_P$1") (pintype "bidirectional"))
    )
    (net (code "4") (name "EXPB") (class "Default")
      (node (ref "C405") (pin "2") (pinfunction "2_2") (pintype "passive"))
      (node (ref "JP101") (pin "3") (pinfunction "3_3") (pintype "passive"))
      (node (ref "R420") (pin "2") (pinfunction "2_2") (pintype "passive"))
      (node (ref "TP37") (pin "P$1") (pinfunction "1_P$1") (pintype "bidirectional"))
    )
    (net (code "5") (name "F1") (class "Default")
      (node (ref "JP101") (pin "12") (pinfunction "12_12") (pintype "passive"))
      (node (ref "S101") (pin "3") (pinfunction "S_3") (pintype "passive"))
      (node (ref "S101") (pin "4") (pinfunction "S1_4") (pintype "passive"))
    )
    (net (code "6") (name "F2") (class "Default")
      (node (ref "JP101") (pin "11") (pinfunction "11_11") (pintype "passive"))
      (node (ref "S101") (pin "1") (pinfunction "P_1") (pintype "passive"))
      (node (ref "S101") (pin "2") (pinfunction "P1_2") (pintype "passive"))
    )
    (net (code "7") (name "GSCLK_") (class "Default")
      (node (ref "C104") (pin "2") (pinfunction "2_2") (pintype "passive"))
      (node (ref "C204") (pin "2") (pinfunction "2_2") (pintype "passive"))
      (node (ref "C304") (pin "2") (pinfunction "2_2") (pintype "passive"))
      (node (ref "C404") (pin "2") (pinfunction "2_2") (pintype "passive"))
      (node (ref "JP101") (pin "5") (pinfunction "5_5") (pintype "passive"))
      (node (ref "TP13") (pin "P$1") (pinfunction "1_P$1") (pintype "bidirectional"))
      (node (ref "TP26") (pin "P$1") (pinfunction "1_P$1") (pintype "bidirectional"))
      (node (ref "TP36") (pin "P$1") (pinfunction "1_P$1") (pintype "bidirectional"))
      (node (ref "TP5") (pin "P$1") (pinfunction "1_P$1") (pintype "bidirectional"))
      (node (ref "U101") (pin "25") (pinfunction "GSCLK_25") (pintype "input"))
      (node (ref "U201") (pin "25") (pinfunction "GSCLK_25") (pintype "input"))
      (node (ref "U301") (pin "25") (pinfunction "GSCLK_25") (pintype "input"))
      (node (ref "U401") (pin "25") (pinfunction "GSCLK_25") (pintype "input"))
    )
    (net (code "8") (name "IR101") (class "Default")
      (node (ref "R120") (pin "2") (pinfunction "2_2") (pintype "passive"))
      (node (ref "R122") (pin "2") (pinfunction "2_2") (pintype "passive"))
      (node (ref "U101") (pin "27") (pinfunction "IREF_27") (pintype "input"))
    )
    (net (code "9") (name "IR201") (class "Default")
      (node (ref "R219") (pin "2") (pinfunction "2_2") (pintype "passive"))
      (node (ref "R221") (pin "2") (pinfunction "2_2") (pintype "passive"))
      (node (ref "U201") (pin "27") (pinfunction "IREF_27") (pintype "input"))
    )
    (net (code "10") (name "IR301") (class "Default")
      (node (ref "R319") (pin "2") (pinfunction "2_2") (pintype "passive"))
      (node (ref "R321") (pin "2") (pinfunction "2_2") (pintype "passive"))
      (node (ref "U301") (pin "27") (pinfunction "IREF_27") (pintype "input"))
    )
    (net (code "11") (name "IR401") (class "Default")
      (node (ref "R419") (pin "2") (pinfunction "2_2") (pintype "passive"))
      (node (ref "R422") (pin "2") (pinfunction "2_2") (pintype "passive"))
      (node (ref "U401") (pin "27") (pinfunction "IREF_27") (pintype "input"))
    )
    (net (code "12") (name "M00") (class "Default")
      (node (ref "R102") (pin "1") (pinfunction "1_1") (pintype "passive"))
      (node (ref "R202") (pin "1") (pinfunction "1_1") (pintype "passive"))
      (node (ref "R302") (pin "1") (pinfunction "1_1") (pintype "passive"))
      (node (ref "R402") (pin "1") (pinfunction "1_1") (pintype "passive"))
      (node (ref "U101") (pin "7") (pinfunction "OUT0_7") (pintype "output"))
      (node (ref "U201") (pin "7") (pinfunction "OUT0_7") (pintype "output"))
      (node (ref "U301") (pin "7") (pinfunction "OUT0_7") (pintype "output"))
      (node (ref "U401") (pin "7") (pinfunction "OUT0_7") (pintype "output"))
    )
    (net (code "13") (name "M01") (class "Default")
      (node (ref "R103") (pin "1") (pinfunction "1_1") (pintype "passive"))
      (node (ref "R203") (pin "1") (pinfunction "1_1") (pintype "passive"))
      (node (ref "R303") (pin "1") (pinfunction "1_1") (pintype "passive"))
      (node (ref "R403") (pin "1") (pinfunction "1_1") (pintype "passive"))
      (node (ref "U101") (pin "8") (pinfunction "OUT1_8") (pintype "output"))
      (node (ref "U201") (pin "8") (pinfunction "OUT1_8") (pintype "output"))
      (node (ref "U301") (pin "8") (pinfunction "OUT1_8") (pintype "output"))
      (node (ref "U401") (pin "8") (pinfunction "OUT1_8") (pintype "output"))
    )
    (net (code "14") (name "M02") (class "Default")
      (node (ref "R104") (pin "1") (pinfunction "1_1") (pintype "passive"))
      (node (ref "R204") (pin "1") (pinfunction "1_1") (pintype "passive"))
      (node (ref "R304") (pin "1") (pinfunction "1_1") (pintype "passive"))
      (node (ref "R404") (pin "1") (pinfunction "1_1") (pintype "passive"))
      (node (ref "U101") (pin "9") (pinfunction "OUT2_9") (pintype "output"))
      (node (ref "U201") (pin "9") (pinfunction "OUT2_9") (pintype "output"))
      (node (ref "U301") (pin "9") (pinfunction "OUT2_9") (pintype "output"))
      (node (ref "U401") (pin "9") (pinfunction "OUT2_9") (pintype "output"))
    )
    (net (code "15") (name "M03") (class "Default")
      (node (ref "R105") (pin "1") (pinfunction "1_1") (pintype "passive"))
      (node (ref "R205") (pin "1") (pinfunction "1_1") (pintype "passive"))
      (node (ref "R305") (pin "1") (pinfunction "1_1") (pintype "passive"))
      (node (ref "R405") (pin "1") (pinfunction "1_1") (pintype "passive"))
      (node (ref "U101") (pin "10") (pinfunction "OUT3_10") (pintype "output"))
      (node (ref "U201") (pin "10") (pinfunction "OUT3_10") (pintype "output"))
      (node (ref "U301") (pin "10") (pinfunction "OUT3_10") (pintype "output"))
      (node (ref "U401") (pin "10") (pinfunction "OUT3_10") (pintype "output"))
    )
    (net (code "16") (name "M04") (class "Default")
      (node (ref "R106") (pin "1") (pinfunction "1_1") (pintype "passive"))
      (node (ref "R206") (pin "1") (pinfunction "1_1") (pintype "passive"))
      (node (ref "R306") (pin "1") (pinfunction "1_1") (pintype "passive"))
      (node (ref "R406") (pin "1") (pinfunction "1_1") (pintype "passive"))
      (node (ref "U101") (pin "11") (pinfunction "OUT4_11") (pintype "output"))
      (node (ref "U201") (pin "11") (pinfunction "OUT4_11") (pintype "output"))
      (node (ref "U301") (pin "11") (pinfunction "OUT4_11") (pintype "output"))
      (node (ref "U401") (pin "11") (pinfunction "OUT4_11") (pintype "output"))
    )
    (net (code "17") (name "M05") (class "Default")
      (node (ref "R107") (pin "1") (pinfunction "1_1") (pintype "passive"))
      (node (ref "R207") (pin "1") (pinfunction "1_1") (pintype "passive"))
      (node (ref "R307") (pin "1") (pinfunction "1_1") (pintype "passive"))
      (node (ref "R407") (pin "1") (pinfunction "1_1") (pintype "passive"))
      (node (ref "U101") (pin "12") (pinfunction "OUT5_12") (pintype "output"))
      (node (ref "U201") (pin "12") (pinfunction "OUT5_12") (pintype "output"))
      (node (ref "U301") (pin "12") (pinfunction "OUT5_12") (pintype "output"))
      (node (ref "U401") (pin "12") (pinfunction "OUT5_12") (pintype "output"))
    )
    (net (code "18") (name "M06") (class "Default")
      (node (ref "R108") (pin "1") (pinfunction "1_1") (pintype "passive"))
      (node (ref "R208") (pin "1") (pinfunction "1_1") (pintype "passive"))
      (node (ref "R308") (pin "1") (pinfunction "1_1") (pintype "passive"))
      (node (ref "R408") (pin "1") (pinfunction "1_1") (pintype "passive"))
      (node (ref "U101") (pin "13") (pinfunction "OUT6_13") (pintype "output"))
      (node (ref "U201") (pin "13") (pinfunction "OUT6_13") (pintype "output"))
      (node (ref "U301") (pin "13") (pinfunction "OUT6_13") (pintype "output"))
      (node (ref "U401") (pin "13") (pinfunction "OUT6_13") (pintype "output"))
    )
    (net (code "19") (name "M07") (class "Default")
      (node (ref "R109") (pin "1") (pinfunction "1_1") (pintype "passive"))
      (node (ref "R209") (pin "1") (pinfunction "1_1") (pintype "passive"))
      (node (ref "R309") (pin "1") (pinfunction "1_1") (pintype "passive"))
      (node (ref "R409") (pin "1") (pinfunction "1_1") (pintype "passive"))
      (node (ref "U101") (pin "14") (pinfunction "OUT7_14") (pintype "output"))
      (node (ref "U201") (pin "14") (pinfunction "OUT7_14") (pintype "output"))
      (node (ref "U301") (pin "14") (pinfunction "OUT7_14") (pintype "output"))
      (node (ref "U401") (pin "14") (pinfunction "OUT7_14") (pintype "output"))
    )
    (net (code "20") (name "M08") (class "Default")
      (node (ref "R110") (pin "1") (pinfunction "1_1") (pintype "passive"))
      (node (ref "R210") (pin "1") (pinfunction "1_1") (pintype "passive"))
      (node (ref "R310") (pin "1") (pinfunction "1_1") (pintype "passive"))
      (node (ref "R410") (pin "1") (pinfunction "1_1") (pintype "passive"))
      (node (ref "U101") (pin "15") (pinfunction "OUT8_15") (pintype "output"))
      (node (ref "U201") (pin "15") (pinfunction "OUT8_15") (pintype "output"))
      (node (ref "U301") (pin "15") (pinfunction "OUT8_15") (pintype "output"))
      (node (ref "U401") (pin "15") (pinfunction "OUT8_15") (pintype "output"))
    )
    (net (code "21") (name "M09") (class "Default")
      (node (ref "R111") (pin "1") (pinfunction "1_1") (pintype "passive"))
      (node (ref "R211") (pin "1") (pinfunction "1_1") (pintype "passive"))
      (node (ref "R311") (pin "1") (pinfunction "1_1") (pintype "passive"))
      (node (ref "R411") (pin "1") (pinfunction "1_1") (pintype "passive"))
      (node (ref "U101") (pin "16") (pinfunction "OUT9_16") (pintype "output"))
      (node (ref "U201") (pin "16") (pinfunction "OUT9_16") (pintype "output"))
      (node (ref "U301") (pin "16") (pinfunction "OUT9_16") (pintype "output"))
      (node (ref "U401") (pin "16") (pinfunction "OUT9_16") (pintype "output"))
    )
    (net (code "22") (name "M10") (class "Default")
      (node (ref "R112") (pin "1") (pinfunction "1_1") (pintype "passive"))
      (node (ref "R212") (pin "1") (pinfunction "1_1") (pintype "passive"))
      (node (ref "R312") (pin "1") (pinfunction "1_1") (pintype "passive"))
      (node (ref "R412") (pin "1") (pinfunction "1_1") (pintype "passive"))
      (node (ref "U101") (pin "17") (pinfunction "OUT10_17") (pintype "output"))
      (node (ref "U201") (pin "17") (pinfunction "OUT10_17") (pintype "output"))
      (node (ref "U301") (pin "17") (pinfunction "OUT10_17") (pintype "output"))
      (node (ref "U401") (pin "17") (pinfunction "OUT10_17") (pintype "output"))
    )
    (net (code "23") (name "M11") (class "Default")
      (node (ref "R113") (pin "1") (pinfunction "1_1") (pintype "passive"))
      (node (ref "R213") (pin "1") (pinfunction "1_1") (pintype "passive"))
      (node (ref "R313") (pin "1") (pinfunction "1_1") (pintype "passive"))
      (node (ref "R413") (pin "1") (pinfunction "1_1") (pintype "passive"))
      (node (ref "U101") (pin "18") (pinfunction "OUT11_18") (pintype "output"))
      (node (ref "U201") (pin "18") (pinfunction "OUT11_18") (pintype "output"))
      (node (ref "U301") (pin "18") (pinfunction "OUT11_18") (pintype "output"))
      (node (ref "U401") (pin "18") (pinfunction "OUT11_18") (pintype "output"))
    )
    (net (code "24") (name "M12") (class "Default")
      (node (ref "R114") (pin "1") (pinfunction "1_1") (pintype "passive"))
      (node (ref "R214") (pin "1") (pinfunction "1_1") (pintype "passive"))
      (node (ref "R314") (pin "1") (pinfunction "1_1") (pintype "passive"))
      (node (ref "R414") (pin "1") (pinfunction "1_1") (pintype "passive"))
      (node (ref "U101") (pin "19") (pinfunction "OUT12_19") (pintype "output"))
      (node (ref "U201") (pin "19") (pinfunction "OUT12_19") (pintype "output"))
      (node (ref "U301") (pin "19") (pinfunction "OUT12_19") (pintype "output"))
      (node (ref "U401") (pin "19") (pinfunction "OUT12_19") (pintype "output"))
    )
    (net (code "25") (name "M13") (class "Default")
      (node (ref "R115") (pin "1") (pinfunction "1_1") (pintype "passive"))
      (node (ref "R215") (pin "1") (pinfunction "1_1") (pintype "passive"))
      (node (ref "R315") (pin "1") (pinfunction "1_1") (pintype "passive"))
      (node (ref "R415") (pin "1") (pinfunction "1_1") (pintype "passive"))
      (node (ref "U101") (pin "20") (pinfunction "OUT13_20") (pintype "output"))
      (node (ref "U201") (pin "20") (pinfunction "OUT13_20") (pintype "output"))
      (node (ref "U301") (pin "20") (pinfunction "OUT13_20") (pintype "output"))
      (node (ref "U401") (pin "20") (pinfunction "OUT13_20") (pintype "output"))
    )
    (net (code "26") (name "M14") (class "Default")
      (node (ref "R117") (pin "1") (pinfunction "1_1") (pintype "passive"))
      (node (ref "R217") (pin "1") (pinfunction "1_1") (pintype "passive"))
      (node (ref "R317") (pin "1") (pinfunction "1_1") (pintype "passive"))
      (node (ref "R417") (pin "1") (pinfunction "1_1") (pintype "passive"))
      (node (ref "U101") (pin "21") (pinfunction "OUT14_21") (pintype "output"))
      (node (ref "U201") (pin "21") (pinfunction "OUT14_21") (pintype "output"))
      (node (ref "U301") (pin "21") (pinfunction "OUT14_21") (pintype "output"))
      (node (ref "U401") (pin "21") (pinfunction "OUT14_21") (pintype "output"))
    )
    (net (code "27") (name "M15") (class "Default")
      (node (ref "R119") (pin "1") (pinfunction "1_1") (pintype "passive"))
      (node (ref "R218") (pin "1") (pinfunction "1_1") (pintype "passive"))
      (node (ref "R318") (pin "1") (pinfunction "1_1") (pintype "passive"))
      (node (ref "R418") (pin "1") (pinfunction "1_1") (pintype "passive"))
      (node (ref "U101") (pin "22") (pinfunction "OUT15_22") (pintype "output"))
      (node (ref "U201") (pin "22") (pinfunction "OUT15_22") (pintype "output"))
      (node (ref "U301") (pin "22") (pinfunction "OUT15_22") (pintype "output"))
      (node (ref "U401") (pin "22") (pinfunction "OUT15_22") (pintype "output"))
    )
    (net (code "28") (name "Net-(TP7-1)") (class "Default")
      (node (ref "TP7") (pin "P$1") (pinfunction "1_P$1") (pintype "bidirectional"))
      (node (ref "U201") (pin "23") (pinfunction "XERR_23") (pintype "output"))
    )
    (net (code "29") (name "Net-(TP15-1)") (class "Default")
      (node (ref "TP15") (pin "P$1") (pinfunction "1_P$1") (pintype "bidirectional"))
      (node (ref "U301") (pin "23") (pinfunction "XERR_23") (pintype "output"))
    )
    (net (code "30") (name "Net-(TP28-1)") (class "Default")
      (node (ref "TP28") (pin "P$1") (pinfunction "1_P$1") (pintype "bidirectional"))
      (node (ref "U101") (pin "23") (pinfunction "XERR_23") (pintype "output"))
    )
    (net (code "31") (name "Net-(TP38-1)") (class "Default")
      (node (ref "TP38") (pin "P$1") (pinfunction "1_P$1") (pintype "bidirectional"))
      (node (ref "U401") (pin "23") (pinfunction "XERR_23") (pintype "output"))
    )
    (net (code "32") (name "Net-(U101-DCPRG)") (class "Default")
      (node (ref "R121") (pin "2") (pinfunction "2_2") (pintype "passive"))
      (node (ref "U101") (pin "26") (pinfunction "DCPRG_26") (pintype "input"))
    )
    (net (code "33") (name "Net-(U101-SIN)") (class "Default")
      (node (ref "C101") (pin "2") (pinfunction "2_2") (pintype "passive"))
      (node (ref "R116") (pin "2") (pinfunction "2_2") (pintype "passive"))
      (node (ref "U101") (pin "5") (pinfunction "SIN_5") (pintype "input"))
    )
    (net (code "34") (name "Net-(U201-DCPRG)") (class "Default")
      (node (ref "R220") (pin "2") (pinfunction "2_2") (pintype "passive"))
      (node (ref "U201") (pin "26") (pinfunction "DCPRG_26") (pintype "input"))
    )
    (net (code "35") (name "Net-(U201-SIN)") (class "Default")
      (node (ref "C201") (pin "2") (pinfunction "2_2") (pintype "passive"))
      (node (ref "R216") (pin "2") (pinfunction "2_2") (pintype "passive"))
      (node (ref "U201") (pin "5") (pinfunction "SIN_5") (pintype "input"))
    )
    (net (code "36") (name "Net-(U301-DCPRG)") (class "Default")
      (node (ref "R320") (pin "2") (pinfunction "2_2") (pintype "passive"))
      (node (ref "U301") (pin "26") (pinfunction "DCPRG_26") (pintype "input"))
    )
    (net (code "37") (name "Net-(U301-SIN)") (class "Default")
      (node (ref "C301") (pin "2") (pinfunction "2_2") (pintype "passive"))
      (node (ref "R316") (pin "2") (pinfunction "2_2") (pintype "passive"))
      (node (ref "U301") (pin "5") (pinfunction "SIN_5") (pintype "input"))
    )
    (net (code "38") (name "Net-(U401-DCPRG)") (class "Default")
      (node (ref "R421") (pin "2") (pinfunction "2_2") (pintype "passive"))
      (node (ref "U401") (pin "26") (pinfunction "DCPRG_26") (pintype "input"))
    )
    (net (code "39") (name "Net-(U401-SIN)") (class "Default")
      (node (ref "C401") (pin "2") (pinfunction "2_2") (pintype "passive"))
      (node (ref "R416") (pin "2") (pinfunction "2_2") (pintype "passive"))
      (node (ref "U401") (pin "5") (pinfunction "SIN_5") (pintype "input"))
    )
    (net (code "40") (name "Net-(U401-SOUT)") (class "Default")
      (node (ref "R420") (pin "1") (pinfunction "1_1") (pintype "passive"))
      (node (ref "U401") (pin "24") (pinfunction "SOUT_24") (pintype "output"))
    )
    (net (code "41") (name "RA") (class "Default")
      (node (ref "JP101") (pin "2") (pinfunction "2_2") (pintype "passive"))
      (node (ref "R118") (pin "2") (pinfunction "2_2") (pintype "passive"))
    )
    (net (code "42") (name "RB") (class "Default")
      (node (ref "JP101") (pin "1") (pinfunction "1_1") (pintype "passive"))
      (node (ref "R118") (pin "1") (pinfunction "1_1") (pintype "passive"))
    )
    (net (code "43") (name "SCLK_") (class "Default")
      (node (ref "C105") (pin "2") (pinfunction "2_2") (pintype "passive"))
      (node (ref "C205") (pin "2") (pinfunction "2_2") (pintype "passive"))
      (node (ref "C305") (pin "2") (pinfunction "2_2") (pintype "passive"))
      (node (ref "C406") (pin "2") (pinfunction "2_2") (pintype "passive"))
      (node (ref "JP101") (pin "6") (pinfunction "6_6") (pintype "passive"))
      (node (ref "TP10") (pin "P$1") (pinfunction "1_P$1") (pintype "bidirectional"))
      (node (ref "TP2") (pin "P$1") (pinfunction "1_P$1") (pintype "bidirectional"))
      (node (ref "TP23") (pin "P$1") (pinfunction "1_P$1") (pintype "bidirectional"))
      (node (ref "TP33") (pin "P$1") (pinfunction "1_P$1") (pintype "bidirectional"))
      (node (ref "U101") (pin "4") (pinfunction "SCLK_4") (pintype "input"))
      (node (ref "U201") (pin "4") (pinfunction "SCLK_4") (pintype "input"))
      (node (ref "U301") (pin "4") (pinfunction "SCLK_4") (pintype "input"))
      (node (ref "U401") (pin "4") (pinfunction "SCLK_4") (pintype "input"))
    )
    (net (code "44") (name "SOUT101") (class "Default")
      (node (ref "R216") (pin "1") (pinfunction "1_1") (pintype "passive"))
      (node (ref "TP1") (pin "P$1") (pinfunction "1_P$1") (pintype "bidirectional"))
      (node (ref "TP27") (pin "P$1") (pinfunction "1_P$1") (pintype "bidirectional"))
      (node (ref "U101") (pin "24") (pinfunction "SOUT_24") (pintype "output"))
    )
    (net (code "45") (name "SOUT201") (class "Default")
      (node (ref "R316") (pin "1") (pinfunction "1_1") (pintype "passive"))
      (node (ref "TP6") (pin "P$1") (pinfunction "1_P$1") (pintype "bidirectional"))
      (node (ref "TP9") (pin "P$1") (pinfunction "1_P$1") (pintype "bidirectional"))
      (node (ref "U201") (pin "24") (pinfunction "SOUT_24") (pintype "output"))
    )
    (net (code "46") (name "SOUT301") (class "Default")
      (node (ref "R416") (pin "1") (pinfunction "1_1") (pintype "passive"))
      (node (ref "TP14") (pin "P$1") (pinfunction "1_P$1") (pintype "bidirectional"))
      (node (ref "TP32") (pin "P$1") (pinfunction "1_P$1") (pintype "bidirectional"))
      (node (ref "U301") (pin "24") (pinfunction "SOUT_24") (pintype "output"))
    )
    (net (code "47") (name "VCC") (class "Default")
      (node (ref "JP101") (pin "14") (pinfunction "14_14") (pintype "passive"))
      (node (ref "JP101") (pin "16") (pinfunction "16_16") (pintype "passive"))
      (node (ref "R102") (pin "2") (pinfunction "2_2") (pintype "passive"))
      (node (ref "R103") (pin "2") (pinfunction "2_2") (pintype "passive"))
      (node (ref "R104") (pin "2") (pinfunction "2_2") (pintype "passive"))
      (node (ref "R105") (pin "2") (pinfunction "2_2") (pintype "passive"))
      (node (ref "R106") (pin "2") (pinfunction "2_2") (pintype "passive"))
      (node (ref "R107") (pin "2") (pinfunction "2_2") (pintype "passive"))
      (node (ref "R108") (pin "2") (pinfunction "2_2") (pintype "passive"))
      (node (ref "R109") (pin "2") (pinfunction "2_2") (pintype "passive"))
      (node (ref "R110") (pin "2") (pinfunction "2_2") (pintype "passive"))
      (node (ref "R111") (pin "2") (pinfunction "2_2") (pintype "passive"))
      (node (ref "R112") (pin "2") (pinfunction "2_2") (pintype "passive"))
      (node (ref "R113") (pin "2") (pinfunction "2_2") (pintype "passive"))
      (node (ref "R114") (pin "2") (pinfunction "2_2") (pintype "passive"))
      (node (ref "R115") (pin "2") (pinfunction "2_2") (pintype "passive"))
      (node (ref "R117") (pin "2") (pinfunction "2_2") (pintype "passive"))
      (node (ref "R119") (pin "2") (pinfunction "2_2") (pintype "passive"))
      (node (ref "R121") (pin "1") (pinfunction "1_1") (pintype "passive"))
      (node (ref "R202") (pin "2") (pinfunction "2_2") (pintype "passive"))
      (node (ref "R203") (pin "2") (pinfunction "2_2") (pintype "passive"))
      (node (ref "R204") (pin "2") (pinfunction "2_2") (pintype "passive"))
      (node (ref "R205") (pin "2") (pinfunction "2_2") (pintype "passive"))
      (node (ref "R206") (pin "2") (pinfunction "2_2") (pintype "passive"))
      (node (ref "R207") (pin "2") (pinfunction "2_2") (pintype "passive"))
      (node (ref "R208") (pin "2") (pinfunction "2_2") (pintype "passive"))
      (node (ref "R209") (pin "2") (pinfunction "2_2") (pintype "passive"))
      (node (ref "R210") (pin "2") (pinfunction "2_2") (pintype "passive"))
      (node (ref "R211") (pin "2") (pinfunction "2_2") (pintype "passive"))
      (node (ref "R212") (pin "2") (pinfunction "2_2") (pintype "passive"))
      (node (ref "R213") (pin "2") (pinfunction "2_2") (pintype "passive"))
      (node (ref "R214") (pin "2") (pinfunction "2_2") (pintype "passive"))
      (node (ref "R215") (pin "2") (pinfunction "2_2") (pintype "passive"))
      (node (ref "R217") (pin "2") (pinfunction "2_2") (pintype "passive"))
      (node (ref "R218") (pin "2") (pinfunction "2_2") (pintype "passive"))
      (node (ref "R220") (pin "1") (pinfunction "1_1") (pintype "passive"))
      (node (ref "R302") (pin "2") (pinfunction "2_2") (pintype "passive"))
      (node (ref "R303") (pin "2") (pinfunction "2_2") (pintype "passive"))
      (node (ref "R304") (pin "2") (pinfunction "2_2") (pintype "passive"))
      (node (ref "R305") (pin "2") (pinfunction "2_2") (pintype "passive"))
      (node (ref "R306") (pin "2") (pinfunction "2_2") (pintype "passive"))
      (node (ref "R307") (pin "2") (pinfunction "2_2") (pintype "passive"))
      (node (ref "R308") (pin "2") (pinfunction "2_2") (pintype "passive"))
      (node (ref "R309") (pin "2") (pinfunction "2_2") (pintype "passive"))
      (node (ref "R310") (pin "2") (pinfunction "2_2") (pintype "passive"))
      (node (ref "R311") (pin "2") (pinfunction "2_2") (pintype "passive"))
      (node (ref "R312") (pin "2") (pinfunction "2_2") (pintype "passive"))
      (node (ref "R313") (pin "2") (pinfunction "2_2") (pintype "passive"))
      (node (ref "R314") (pin "2") (pinfunction "2_2") (pintype "passive"))
      (node (ref "R315") (pin "2") (pinfunction "2_2") (pintype "passive"))
      (node (ref "R317") (pin "2") (pinfunction "2_2") (pintype "passive"))
      (node (ref "R318") (pin "2") (pinfunction "2_2") (pintype "passive"))
      (node (ref "R320") (pin "1") (pinfunction "1_1") (pintype "passive"))
      (node (ref "R402") (pin "2") (pinfunction "2_2") (pintype "passive"))
      (node (ref "R403") (pin "2") (pinfunction "2_2") (pintype "passive"))
      (node (ref "R404") (pin "2") (pinfunction "2_2") (pintype "passive"))
      (node (ref "R405") (pin "2") (pinfunction "2_2") (pintype "passive"))
      (node (ref "R406") (pin "2") (pinfunction "2_2") (pintype "passive"))
      (node (ref "R407") (pin "2") (pinfunction "2_2") (pintype "passive"))
      (node (ref "R408") (pin "2") (pinfunction "2_2") (pintype "passive"))
      (node (ref "R409") (pin "2") (pinfunction "2_2") (pintype "passive"))
      (node (ref "R410") (pin "2") (pinfunction "2_2") (pintype "passive"))
      (node (ref "R411") (pin "2") (pinfunction "2_2") (pintype "passive"))
      (node (ref "R412") (pin "2") (pinfunction "2_2") (pintype "passive"))
      (node (ref "R413") (pin "2") (pinfunction "2_2") (pintype "passive"))
      (node (ref "R414") (pin "2") (pinfunction "2_2") (pintype "passive"))
      (node (ref "R415") (pin "2") (pinfunction "2_2") (pintype "passive"))
      (node (ref "R417") (pin "2") (pinfunction "2_2") (pintype "passive"))
      (node (ref "R418") (pin "2") (pinfunction "2_2") (pintype "passive"))
      (node (ref "R421") (pin "1") (pinfunction "1_1") (pintype "passive"))
      (node (ref "U101") (pin "28") (pinfunction "VCC_28") (pintype "power_in"))
      (node (ref "U201") (pin "28") (pinfunction "VCC_28") (pintype "power_in"))
      (node (ref "U301") (pin "28") (pinfunction "VCC_28") (pintype "power_in"))
      (node (ref "U401") (pin "28") (pinfunction "VCC_28") (pintype "power_in"))
    )
    (net (code "48") (name "VPRG_") (class "Default")
      (node (ref "JP101") (pin "10") (pinfunction "10_10") (pintype "passive"))
      (node (ref "R101") (pin "1") (pinfunction "1_1") (pintype "passive"))
      (node (ref "R201") (pin "1") (pinfunction "1_1") (pintype "passive"))
      (node (ref "R301") (pin "1") (pinfunction "1_1") (pintype "passive"))
      (node (ref "R401") (pin "1") (pinfunction "1_1") (pintype "passive"))
      (node (ref "U101") (pin "6") (pinfunction "VPRG_6") (pintype "input"))
      (node (ref "U201") (pin "6") (pinfunction "VPRG_6") (pintype "input"))
      (node (ref "U301") (pin "6") (pinfunction "VPRG_6") (pintype "input"))
      (node (ref "U401") (pin "6") (pinfunction "VPRG_6") (pintype "input"))
    )
    (net (code "49") (name "XLAT_") (class "Default")
      (node (ref "C102") (pin "2") (pinfunction "2_2") (pintype "passive"))
      (node (ref "C202") (pin "2") (pinfunction "2_2") (pintype "passive"))
      (node (ref "C302") (pin "2") (pinfunction "2_2") (pintype "passive"))
      (node (ref "C402") (pin "2") (pinfunction "2_2") (pintype "passive"))
      (node (ref "JP101") (pin "8") (pinfunction "8_8") (pintype "passive"))
      (node (ref "TP11") (pin "P$1") (pinfunction "1_P$1") (pintype "bidirectional"))
      (node (ref "TP24") (pin "P$1") (pinfunction "1_P$1") (pintype "bidirectional"))
      (node (ref "TP3") (pin "P$1") (pinfunction "1_P$1") (pintype "bidirectional"))
      (node (ref "TP34") (pin "P$1") (pinfunction "1_P$1") (pintype "bidirectional"))
      (node (ref "U101") (pin "3") (pinfunction "XLAT_3") (pintype "input"))
      (node (ref "U201") (pin "3") (pinfunction "XLAT_3") (pintype "input"))
      (node (ref "U301") (pin "3") (pinfunction "XLAT_3") (pintype "input"))
      (node (ref "U401") (pin "3") (pinfunction "XLAT_3") (pintype "input"))
    )
    (net (code "50") (name "unconnected-(JP101-Pad9)") (class "Default")
      (node (ref "JP101") (pin "9") (pinfunction "9_9") (pintype "passive"))
    )
  )
)
